# Alarmsystem.net
KiCad netlist of a schematic drawn in EAGLE
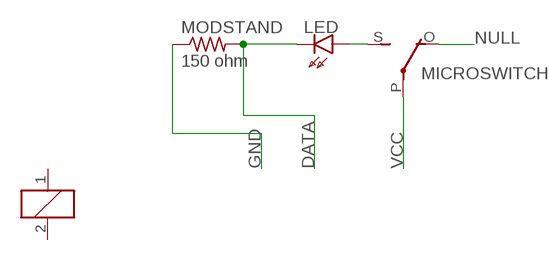
[diagram p0: schematic, sheet 1]

(export (version "E")
  (design (tool "Eeschema 10.0.6"))
  (components
    (comp (ref "LED")
      (value "HLMP6")
      (footprint "eagle-import:HLMP6")
      (fields (field (name "MF") "AGILENT TECHNOLOGIES") (field (name "MPN") "HLMP-6500"))
      (libsource (lib "eagle-import") (part "HLMP6"))
    )
    (comp (ref "MICROSWITCH")
      (value "E3206S")
      (footprint "eagle-import:E3206S")
      (libsource (lib "eagle-import") (part "E3206S"))
    )
    (comp (ref "MODSTAND")
      (value "150 ohm")
      (footprint "eagle-import:0204_7")
      (libsource (lib "eagle-import") (part "R-US_0204/7"))
    )
  )
  (nets
    (net (code "1") (name "/DATA") (class "Default")
      (node (ref "LED") (pin "K") (pinfunction "K_K") (pintype "passive"))
      (node (ref "MODSTAND") (pin "2") (pinfunction "2_2") (pintype "passive"))
    )
    (net (code "2") (name "/GND") (class "Default")
      (node (ref "MODSTAND") (pin "1") (pinfunction "1_1") (pintype "passive"))
    )
    (net (code "3") (name "/NULL") (class "Default")
      (node (ref "MICROSWITCH") (pin "O") (pinfunction "O_O") (pintype "passive"))
    )
    (net (code "4") (name "/VCC") (class "Default")
      (node (ref "MICROSWITCH") (pin "P") (pinfunction "P_P") (pintype "passive"))
    )
    (net (code "5") (name "Net-(LED-PadA)") (class "Default")
      (node (ref "LED") (pin "A") (pinfunction "A_A") (pintype "passive"))
      (node (ref "MICROSWITCH") (pin "S") (pinfunction "S_S") (pintype "passive"))
    )
    (net (code "6") (name "unconnected-(MICROSWITCH-Pad1)") (class "Default")
      (node (ref "MICROSWITCH") (pin "1") (pinfunction "1_1") (pintype "passive"))
    )
    (net (code "7") (name "unconnected-(MICROSWITCH-Pad2)") (class "Default")
      (node (ref "MICROSWITCH") (pin "2") (pinfunction "2_2") (pintype "passive"))
    )
  )
)
